# OK6010_DB.net
KiCad netlist of a schematic drawn in Altium Designer
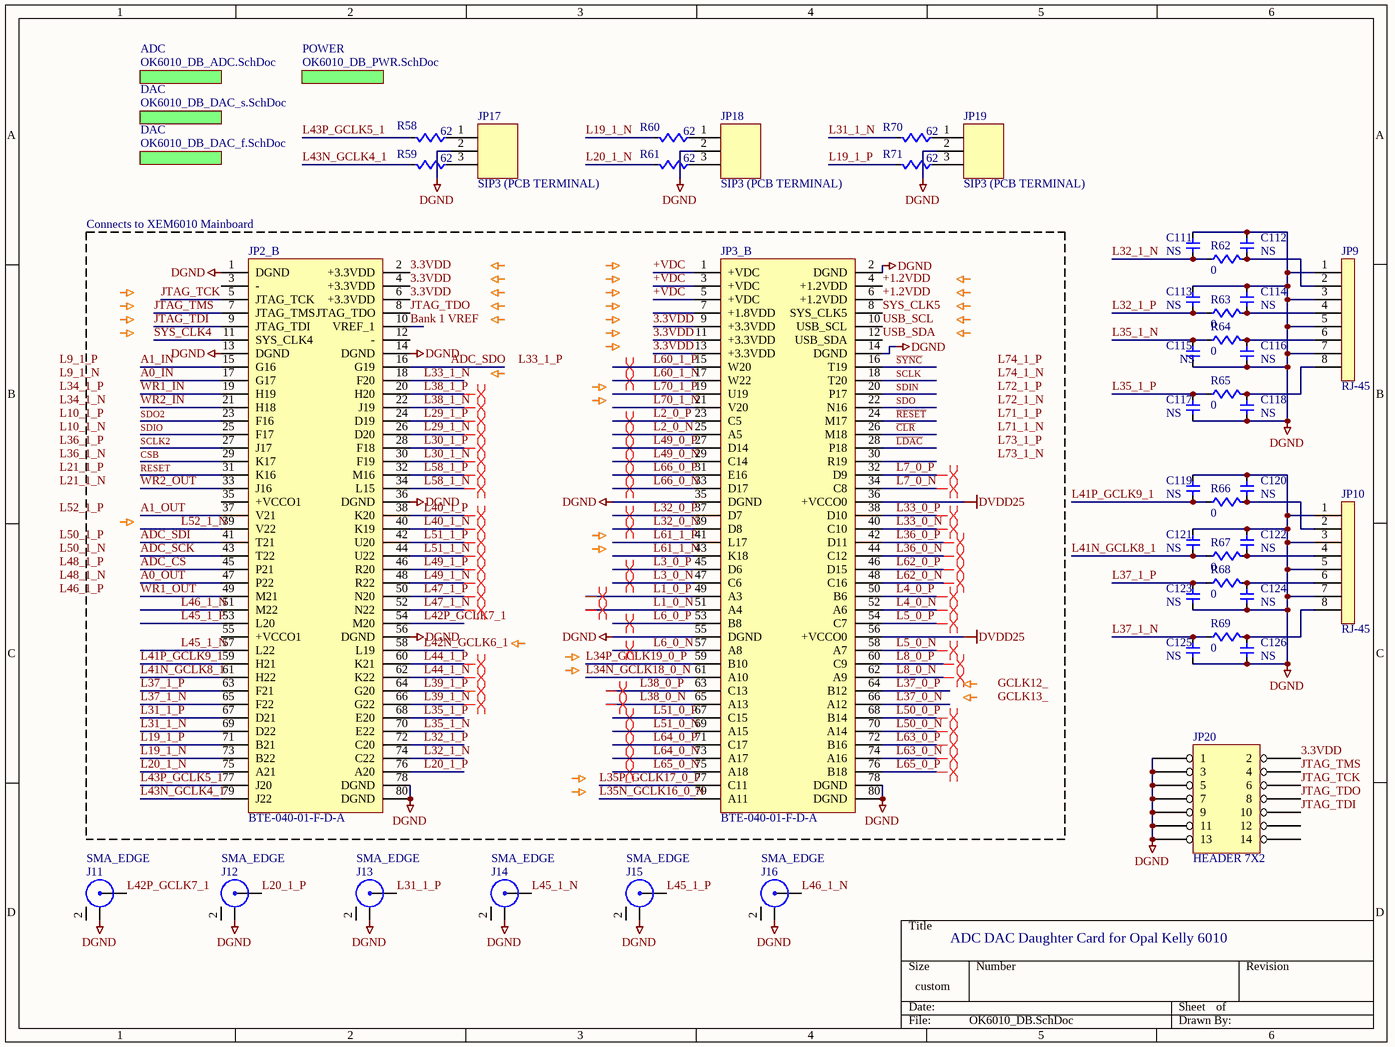
[diagram p0: OK6010_DB.SchDoc]

(export (version "E")
  (design (tool "Eeschema 10.0.6"))
  (components
    (comp (ref "C111")
      (value "NS")
      (footprint "0603w")
      (description "capacitor")
      (libsource (lib "Device02_remote") (part "CAP_SM"))
    )
    (comp (ref "C112")
      (value "NS")
      (footprint "0603w")
      (description "capacitor")
      (libsource (lib "Device02_remote") (part "CAP_SM"))
    )
    (comp (ref "C113")
      (value "NS")
      (footprint "0603w")
      (description "capacitor")
      (libsource (lib "Device02_remote") (part "CAP_SM"))
    )
    (comp (ref "C114")
      (value "NS")
      (footprint "0603w")
      (description "capacitor")
      (libsource (lib "Device02_remote") (part "CAP_SM"))
    )
    (comp (ref "C115")
      (value "NS")
      (footprint "0603w")
      (description "capacitor")
      (libsource (lib "Device02_remote") (part "CAP_SM"))
    )
    (comp (ref "C116")
      (value "NS")
      (footprint "0603w")
      (description "capacitor")
      (libsource (lib "Device02_remote") (part "CAP_SM"))
    )
    (comp (ref "C117")
      (value "NS")
      (footprint "0603w")
      (description "capacitor")
      (libsource (lib "Device02_remote") (part "CAP_SM"))
    )
    (comp (ref "C118")
      (value "NS")
      (footprint "0603w")
      (description "capacitor")
      (libsource (lib "Device02_remote") (part "CAP_SM"))
    )
    (comp (ref "C119")
      (value "NS")
      (footprint "0603w")
      (description "capacitor")
      (libsource (lib "Device02_remote") (part "CAP_SM"))
    )
    (comp (ref "C120")
      (value "NS")
      (footprint "0603w")
      (description "capacitor")
      (libsource (lib "Device02_remote") (part "CAP_SM"))
    )
    (comp (ref "C121")
      (value "NS")
      (footprint "0603w")
      (description "capacitor")
      (libsource (lib "Device02_remote") (part "CAP_SM"))
    )
    (comp (ref "C122")
      (value "NS")
      (footprint "0603w")
      (description "capacitor")
      (libsource (lib "Device02_remote") (part "CAP_SM"))
    )
    (comp (ref "C123")
      (value "NS")
      (footprint "0603w")
      (description "capacitor")
      (libsource (lib "Device02_remote") (part "CAP_SM"))
    )
    (comp (ref "C124")
      (value "NS")
      (footprint "0603w")
      (description "capacitor")
      (libsource (lib "Device02_remote") (part "CAP_SM"))
    )
    (comp (ref "C125")
      (value "NS")
      (footprint "0603w")
      (description "capacitor")
      (libsource (lib "Device02_remote") (part "CAP_SM"))
    )
    (comp (ref "C126")
      (value "NS")
      (footprint "0603w")
      (description "capacitor")
      (libsource (lib "Device02_remote") (part "CAP_SM"))
    )
    (comp (ref "J11")
      (value "SMA_EDGE")
      (footprint "sma_edge")
      (description "sma edge connector")
      (libsource (lib "Device02_remote") (part "SMA_EDGE"))
    )
    (comp (ref "J12")
      (value "SMA_EDGE")
      (footprint "sma_edge")
      (description "sma edge connector")
      (libsource (lib "Device02_remote") (part "SMA_EDGE"))
    )
    (comp (ref "J13")
      (value "SMA_EDGE")
      (footprint "sma_edge")
      (description "sma edge connector")
      (libsource (lib "Device02_remote") (part "SMA_EDGE"))
    )
    (comp (ref "J14")
      (value "SMA_EDGE")
      (footprint "sma_edge")
      (description "sma edge connector")
      (libsource (lib "Device02_remote") (part "SMA_EDGE"))
    )
    (comp (ref "J15")
      (value "SMA_EDGE")
      (footprint "sma_edge")
      (description "sma edge connector")
      (libsource (lib "Device02_remote") (part "SMA_EDGE"))
    )
    (comp (ref "J16")
      (value "SMA_EDGE")
      (footprint "sma_edge")
      (description "sma edge connector")
      (libsource (lib "Device02_remote") (part "SMA_EDGE"))
    )
    (comp (ref "JP2_B")
      (value "BTE-040-01-F-D-A")
      (footprint "BTE-040-01-F-D-A")
      (description "Samtec Connector 0.8mm 80pin")
      (libsource (lib "Device02_remote") (part "BTE-040-01-F-D-A XEM6010_JP2"))
    )
    (comp (ref "JP3_B")
      (value "BTE-040-01-F-D-A")
      (footprint "BTE-040-01-F-D-A")
      (description "Samtec Connector 0.8mm 80pin")
      (libsource (lib "Device02_remote") (part "BTE-040-01-F-D-A XEM6010_JP3"))
    )
    (comp (ref "JP9")
      (value "RJ-45")
      (footprint "SMD_ETHERNET")
      (description "ethernet connector")
      (libsource (lib "Device02_remote") (part "SIP8"))
    )
    (comp (ref "JP10")
      (value "RJ-45")
      (footprint "SMD_ETHERNET")
      (description "ethernet connector")
      (libsource (lib "Device02_remote") (part "SIP8"))
    )
    (comp (ref "JP17")
      (value "SIP3 (PCB TERMINAL)")
      (footprint "SIP3MOLEX")
      (description "3 pin molex connector")
      (libsource (lib "Device02_remote") (part "SIP3 (PCB TERMINAL)"))
    )
    (comp (ref "JP18")
      (value "SIP3 (PCB TERMINAL)")
      (footprint "SIP3MOLEX")
      (description "3 pin molex connector")
      (libsource (lib "Device02_remote") (part "SIP3 (PCB TERMINAL)"))
    )
    (comp (ref "JP19")
      (value "SIP3 (PCB TERMINAL)")
      (footprint "SIP3MOLEX")
      (description "3 pin molex connector")
      (libsource (lib "Device02_remote") (part "SIP3 (PCB TERMINAL)"))
    )
    (comp (ref "JP20")
      (value "HEADER 7X2")
      (footprint "IDC14 SM 2MM")
      (description "14 pin 2mm IDC connector")
      (libsource (lib "Device02_remote") (part "HEADER 7X2"))
    )
    (comp (ref "R58")
      (value "62")
      (footprint "0603w")
      (description "resistor")
      (libsource (lib "Device02_remote") (part "RES_SM"))
    )
    (comp (ref "R59")
      (value "62")
      (footprint "0603w")
      (description "resistor")
      (libsource (lib "Device02_remote") (part "RES_SM"))
    )
    (comp (ref "R60")
      (value "62")
      (footprint "0603w")
      (description "resistor")
      (libsource (lib "Device02_remote") (part "RES_SM"))
    )
    (comp (ref "R61")
      (value "62")
      (footprint "0603w")
      (description "resistor")
      (libsource (lib "Device02_remote") (part "RES_SM"))
    )
    (comp (ref "R62")
      (value "0")
      (footprint "0603w")
      (description "resistor")
      (libsource (lib "Device02_remote") (part "RES_SM"))
    )
    (comp (ref "R63")
      (value "0")
      (footprint "0603w")
      (description "resistor")
      (libsource (lib "Device02_remote") (part "RES_SM"))
    )
    (comp (ref "R64")
      (value "0")
      (footprint "0603w")
      (description "resistor")
      (libsource (lib "Device02_remote") (part "RES_SM"))
    )
    (comp (ref "R65")
      (value "0")
      (footprint "0603w")
      (description "resistor")
      (libsource (lib "Device02_remote") (part "RES_SM"))
    )
    (comp (ref "R66")
      (value "0")
      (footprint "0603w")
      (description "resistor")
      (libsource (lib "Device02_remote") (part "RES_SM"))
    )
    (comp (ref "R67")
      (value "0")
      (footprint "0603w")
      (description "resistor")
      (libsource (lib "Device02_remote") (part "RES_SM"))
    )
    (comp (ref "R68")
      (value "0")
      (footprint "0603w")
      (description "resistor")
      (libsource (lib "Device02_remote") (part "RES_SM"))
    )
    (comp (ref "R69")
      (value "0")
      (footprint "0603w")
      (description "resistor")
      (libsource (lib "Device02_remote") (part "RES_SM"))
    )
    (comp (ref "R70")
      (value "62")
      (footprint "0603w")
      (description "resistor")
      (libsource (lib "Device02_remote") (part "RES_SM"))
    )
    (comp (ref "R71")
      (value "62")
      (footprint "0603w")
      (description "resistor")
      (libsource (lib "Device02_remote") (part "RES_SM"))
    )
  )
  (nets
    (net (code "1") (name "/+1.2VDD") (class "Default")
      (node (ref "JP3_B") (pin "4") (pinfunction "+1.2VDD_4") (pintype "passive"))
      (node (ref "JP3_B") (pin "6") (pinfunction "+1.2VDD_6") (pintype "passive"))
    )
    (net (code "2") (name "/+VDC") (class "Default")
      (node (ref "JP3_B") (pin "1") (pinfunction "+VDC_1") (pintype "passive"))
      (node (ref "JP3_B") (pin "3") (pinfunction "+VDC_3") (pintype "passive"))
      (node (ref "JP3_B") (pin "5") (pinfunction "+VDC_5") (pintype "passive"))
    )
    (net (code "3") (name "/3.3VDD") (class "Default")
      (node (ref "JP20") (pin "2") (pinfunction "2_2") (pintype "passive"))
      (node (ref "JP2_B") (pin "2") (pinfunction "+3.3VDD_2") (pintype "passive"))
      (node (ref "JP2_B") (pin "4") (pinfunction "+3.3VDD_4") (pintype "passive"))
      (node (ref "JP2_B") (pin "6") (pinfunction "+3.3VDD_6") (pintype "passive"))
      (node (ref "JP3_B") (pin "11") (pinfunction "+3.3VDD_11") (pintype "passive"))
      (node (ref "JP3_B") (pin "13") (pinfunction "+3.3VDD_13") (pintype "passive"))
      (node (ref "JP3_B") (pin "9") (pinfunction "+3.3VDD_9") (pintype "passive"))
    )
    (net (code "4") (name "/A0_IN") (class "Default")
      (node (ref "JP2_B") (pin "17") (pinfunction "G17_17") (pintype "passive"))
    )
    (net (code "5") (name "/A0_OUT") (class "Default")
      (node (ref "JP2_B") (pin "47") (pinfunction "P22_47") (pintype "passive"))
    )
    (net (code "6") (name "/A1_IN") (class "Default")
      (node (ref "JP2_B") (pin "15") (pinfunction "G16_15") (pintype "passive"))
    )
    (net (code "7") (name "/A1_OUT") (class "Default")
      (node (ref "JP2_B") (pin "37") (pinfunction "V21_37") (pintype "passive"))
    )
    (net (code "8") (name "/ADC_CS") (class "Default")
      (node (ref "JP2_B") (pin "45") (pinfunction "P21_45") (pintype "passive"))
    )
    (net (code "9") (name "/ADC_SCK") (class "Default")
      (node (ref "JP2_B") (pin "43") (pinfunction "T22_43") (pintype "passive"))
    )
    (net (code "10") (name "/ADC_SDI") (class "Default")
      (node (ref "JP2_B") (pin "41") (pinfunction "T21_41") (pintype "passive"))
    )
    (net (code "11") (name "/ADC_SDO") (class "Default")
      (node (ref "JP2_B") (pin "16") (pinfunction "G19_16") (pintype "passive"))
    )
    (net (code "12") (name "/Bank 1 VREF") (class "Default")
      (node (ref "JP2_B") (pin "10") (pinfunction "VREF_1_10") (pintype "passive"))
    )
    (net (code "13") (name "/CSB") (class "Default")
      (node (ref "JP2_B") (pin "29") (pinfunction "K17_29") (pintype "passive"))
    )
    (net (code "16") (name "/JTAG_TCK") (class "Default")
      (node (ref "JP20") (pin "6") (pinfunction "6_6") (pintype "passive"))
      (node (ref "JP2_B") (pin "5") (pinfunction "JTAG_TCK_5") (pintype "passive"))
    )
    (net (code "17") (name "/JTAG_TDI") (class "Default")
      (node (ref "JP20") (pin "10") (pinfunction "10_10") (pintype "passive"))
      (node (ref "JP2_B") (pin "9") (pinfunction "JTAG_TDI_9") (pintype "passive"))
    )
    (net (code "18") (name "/JTAG_TDO") (class "Default")
      (node (ref "JP20") (pin "8") (pinfunction "8_8") (pintype "passive"))
      (node (ref "JP2_B") (pin "8") (pinfunction "JTAG_TDO_8") (pintype "passive"))
    )
    (net (code "19") (name "/JTAG_TMS") (class "Default")
      (node (ref "JP20") (pin "4") (pinfunction "4_4") (pintype "passive"))
      (node (ref "JP2_B") (pin "7") (pinfunction "JTAG_TMS_7") (pintype "passive"))
    )
    (net (code "20") (name "/L1_0_N") (class "Default")
      (node (ref "JP3_B") (pin "51") (pinfunction "A4_51") (pintype "passive"))
    )
    (net (code "21") (name "/L1_0_P") (class "Default")
      (node (ref "JP3_B") (pin "49") (pinfunction "A3_49") (pintype "passive"))
    )
    (net (code "22") (name "/L2_0_N") (class "Default")
      (node (ref "JP3_B") (pin "25") (pinfunction "A5_25") (pintype "passive"))
    )
    (net (code "23") (name "/L2_0_P") (class "Default")
      (node (ref "JP3_B") (pin "23") (pinfunction "C5_23") (pintype "passive"))
    )
    (net (code "24") (name "/L3_0_N") (class "Default")
      (node (ref "JP3_B") (pin "47") (pinfunction "C6_47") (pintype "passive"))
    )
    (net (code "25") (name "/L3_0_P") (class "Default")
      (node (ref "JP3_B") (pin "45") (pinfunction "D6_45") (pintype "passive"))
    )
    (net (code "26") (name "/L4_0_N") (class "Default")
      (node (ref "JP3_B") (pin "52") (pinfunction "A6_52") (pintype "passive"))
    )
    (net (code "27") (name "/L4_0_P") (class "Default")
      (node (ref "JP3_B") (pin "50") (pinfunction "B6_50") (pintype "passive"))
    )
    (net (code "28") (name "/L5_0_N") (class "Default")
      (node (ref "JP3_B") (pin "58") (pinfunction "A7_58") (pintype "passive"))
    )
    (net (code "29") (name "/L5_0_P") (class "Default")
      (node (ref "JP3_B") (pin "54") (pinfunction "C7_54") (pintype "passive"))
    )
    (net (code "30") (name "/L6_0_N") (class "Default")
      (node (ref "JP3_B") (pin "57") (pinfunction "A8_57") (pintype "passive"))
    )
    (net (code "31") (name "/L6_0_P") (class "Default")
      (node (ref "JP3_B") (pin "53") (pinfunction "B8_53") (pintype "passive"))
    )
    (net (code "32") (name "/L7_0_N") (class "Default")
      (node (ref "JP3_B") (pin "34") (pinfunction "C8_34") (pintype "passive"))
    )
    (net (code "33") (name "/L7_0_P") (class "Default")
      (node (ref "JP3_B") (pin "32") (pinfunction "D9_32") (pintype "passive"))
    )
    (net (code "34") (name "/L8_0_N") (class "Default")
      (node (ref "JP3_B") (pin "62") (pinfunction "A9_62") (pintype "passive"))
    )
    (net (code "35") (name "/L8_0_P") (class "Default")
      (node (ref "JP3_B") (pin "60") (pinfunction "C9_60") (pintype "passive"))
    )
    (net (code "40") (name "/L19_1_N") (class "Default")
      (node (ref "JP2_B") (pin "73") (pinfunction "B22_73") (pintype "passive"))
      (node (ref "R60") (pin "2") (pintype "passive"))
    )
    (net (code "41") (name "/L19_1_P") (class "Default")
      (node (ref "JP2_B") (pin "71") (pinfunction "B21_71") (pintype "passive"))
      (node (ref "R71") (pin "2") (pintype "passive"))
    )
    (net (code "42") (name "/L20_1_N") (class "Default")
      (node (ref "JP2_B") (pin "75") (pinfunction "A21_75") (pintype "passive"))
      (node (ref "R61") (pin "2") (pintype "passive"))
    )
    (net (code "43") (name "/L20_1_P") (class "Default")
      (node (ref "J12") (pin "1") (pinfunction "signal_1") (pintype "passive"))
      (node (ref "JP2_B") (pin "76") (pinfunction "A20_76") (pintype "passive"))
    )
    (net (code "46") (name "/L29_1_N") (class "Default")
      (node (ref "JP2_B") (pin "26") (pinfunction "D20_26") (pintype "passive"))
    )
    (net (code "47") (name "/L29_1_P") (class "Default")
      (node (ref "JP2_B") (pin "24") (pinfunction "D19_24") (pintype "passive"))
    )
    (net (code "48") (name "/L30_1_N") (class "Default")
      (node (ref "JP2_B") (pin "30") (pinfunction "F19_30") (pintype "passive"))
    )
    (net (code "49") (name "/L30_1_P") (class "Default")
      (node (ref "JP2_B") (pin "28") (pinfunction "F18_28") (pintype "passive"))
    )
    (net (code "50") (name "/L31_1_N") (class "Default")
      (node (ref "JP2_B") (pin "69") (pinfunction "D22_69") (pintype "passive"))
      (node (ref "R70") (pin "2") (pintype "passive"))
    )
    (net (code "51") (name "/L31_1_P") (class "Default")
      (node (ref "J13") (pin "1") (pinfunction "signal_1") (pintype "passive"))
      (node (ref "JP2_B") (pin "67") (pinfunction "D21_67") (pintype "passive"))
    )
    (net (code "52") (name "/L32_0_N") (class "Default")
      (node (ref "JP3_B") (pin "39") (pinfunction "D8_39") (pintype "passive"))
    )
    (net (code "53") (name "/L32_0_P") (class "Default")
      (node (ref "JP3_B") (pin "37") (pinfunction "D7_37") (pintype "passive"))
    )
    (net (code "54") (name "/L32_1_N") (class "Default")
      (node (ref "C111") (pin "2") (pintype "passive"))
      (node (ref "JP2_B") (pin "74") (pinfunction "C22_74") (pintype "passive"))
      (node (ref "R62") (pin "1") (pintype "passive"))
    )
    (net (code "55") (name "/L32_1_P") (class "Default")
      (node (ref "C113") (pin "2") (pintype "passive"))
      (node (ref "JP2_B") (pin "72") (pinfunction "C20_72") (pintype "passive"))
      (node (ref "R63") (pin "1") (pintype "passive"))
    )
    (net (code "56") (name "/L33_0_N") (class "Default")
      (node (ref "JP3_B") (pin "40") (pinfunction "C10_40") (pintype "passive"))
    )
    (net (code "57") (name "/L33_0_P") (class "Default")
      (node (ref "JP3_B") (pin "38") (pinfunction "D10_38") (pintype "passive"))
    )
    (net (code "58") (name "/L33_1_N") (class "Default")
      (node (ref "JP2_B") (pin "18") (pinfunction "F20_18") (pintype "passive"))
    )
    (net (code "60") (name "/L34N_GCLK18_0_N") (class "Default")
      (node (ref "JP3_B") (pin "61") (pinfunction "A10_61") (pintype "passive"))
    )
    (net (code "61") (name "/L34P_GCLK19_0_P") (class "Default")
      (node (ref "JP3_B") (pin "59") (pinfunction "B10_59") (pintype "passive"))
    )
    (net (code "64") (name "/L35N_GCLK16_0_N") (class "Default")
      (node (ref "JP3_B") (pin "79") (pinfunction "A11_79") (pintype "passive"))
    )
    (net (code "65") (name "/L35P_GCLK17_0_P") (class "Default")
      (node (ref "JP3_B") (pin "77") (pinfunction "C11_77") (pintype "passive"))
    )
    (net (code "66") (name "/L35_1_N") (class "Default")
      (node (ref "C115") (pin "1") (pintype "passive"))
      (node (ref "JP2_B") (pin "70") (pinfunction "E22_70") (pintype "passive"))
      (node (ref "R64") (pin "1") (pintype "passive"))
    )
    (net (code "67") (name "/L35_1_P") (class "Default")
      (node (ref "C117") (pin "1") (pintype "passive"))
      (node (ref "JP2_B") (pin "68") (pinfunction "E20_68") (pintype "passive"))
      (node (ref "R65") (pin "1") (pintype "passive"))
    )
    (net (code "68") (name "/L36_0_N") (class "Default")
      (node (ref "JP3_B") (pin "44") (pinfunction "C12_44") (pintype "passive"))
    )
    (net (code "69") (name "/L36_0_P") (class "Default")
      (node (ref "JP3_B") (pin "42") (pinfunction "D11_42") (pintype "passive"))
    )
    (net (code "72") (name "/L37_0_N") (class "Default")
      (node (ref "JP3_B") (pin "66") (pinfunction "A12_66") (pintype "passive"))
    )
    (net (code "73") (name "/L37_0_P") (class "Default")
      (node (ref "JP3_B") (pin "64") (pinfunction "B12_64") (pintype "passive"))
    )
    (net (code "74") (name "/L37_1_N") (class "Default")
      (node (ref "C125") (pin "1") (pintype "passive"))
      (node (ref "JP2_B") (pin "65") (pinfunction "F22_65") (pintype "passive"))
      (node (ref "R69") (pin "1") (pintype "passive"))
    )
    (net (code "75") (name "/L37_1_P") (class "Default")
      (node (ref "C123") (pin "1") (pintype "passive"))
      (node (ref "JP2_B") (pin "63") (pinfunction "F21_63") (pintype "passive"))
      (node (ref "R68") (pin "1") (pintype "passive"))
    )
    (net (code "76") (name "/L38_0_N") (class "Default")
      (node (ref "JP3_B") (pin "65") (pinfunction "A13_65") (pintype "passive"))
    )
    (net (code "77") (name "/L38_0_P") (class "Default")
      (node (ref "JP3_B") (pin "63") (pinfunction "C13_63") (pintype "passive"))
    )
    (net (code "78") (name "/L38_1_N") (class "Default")
      (node (ref "JP2_B") (pin "22") (pinfunction "J19_22") (pintype "passive"))
    )
    (net (code "79") (name "/L38_1_P") (class "Default")
      (node (ref "JP2_B") (pin "20") (pinfunction "H20_20") (pintype "passive"))
    )
    (net (code "80") (name "/L39_1_N") (class "Default")
      (node (ref "JP2_B") (pin "66") (pinfunction "G22_66") (pintype "passive"))
    )
    (net (code "81") (name "/L39_1_P") (class "Default")
      (node (ref "JP2_B") (pin "64") (pinfunction "G20_64") (pintype "passive"))
    )
    (net (code "82") (name "/L40_1_N") (class "Default")
      (node (ref "JP2_B") (pin "40") (pinfunction "K19_40") (pintype "passive"))
    )
    (net (code "83") (name "/L40_1_P") (class "Default")
      (node (ref "JP2_B") (pin "38") (pinfunction "K20_38") (pintype "passive"))
    )
    (net (code "84") (name "/L41N_GCLK8_1") (class "Default")
      (node (ref "C121") (pin "2") (pintype "passive"))
      (node (ref "JP2_B") (pin "61") (pinfunction "H22_61") (pintype "passive"))
      (node (ref "R67") (pin "1") (pintype "passive"))
    )
    (net (code "85") (name "/L41P_GCLK9_1") (class "Default")
      (node (ref "C119") (pin "2") (pintype "passive"))
      (node (ref "JP2_B") (pin "59") (pinfunction "H21_59") (pintype "passive"))
      (node (ref "R66") (pin "1") (pintype "passive"))
    )
    (net (code "86") (name "/L42N_GCLK6_1") (class "Default")
      (node (ref "JP2_B") (pin "58") (pinfunction "L19_58") (pintype "passive"))
    )
    (net (code "87") (name "/L42P_GCLK7_1") (class "Default")
      (node (ref "J11") (pin "1") (pinfunction "signal_1") (pintype "passive"))
      (node (ref "JP2_B") (pin "54") (pinfunction "M20_54") (pintype "passive"))
    )
    (net (code "88") (name "/L43N_GCLK4_1") (class "Default")
      (node (ref "JP2_B") (pin "79") (pinfunction "J22_79") (pintype "passive"))
      (node (ref "R59") (pin "2") (pintype "passive"))
    )
    (net (code "89") (name "/L43P_GCLK5_1") (class "Default")
      (node (ref "JP2_B") (pin "77") (pinfunction "J20_77") (pintype "passive"))
      (node (ref "R58") (pin "2") (pintype "passive"))
    )
    (net (code "90") (name "/L44_1_N") (class "Default")
      (node (ref "JP2_B") (pin "62") (pinfunction "K22_62") (pintype "passive"))
    )
    (net (code "91") (name "/L44_1_P") (class "Default")
      (node (ref "JP2_B") (pin "60") (pinfunction "K21_60") (pintype "passive"))
    )
    (net (code "92") (name "/L45_1_N") (class "Default")
      (node (ref "J14") (pin "1") (pinfunction "signal_1") (pintype "passive"))
      (node (ref "JP2_B") (pin "57") (pinfunction "L22_57") (pintype "passive"))
    )
    (net (code "93") (name "/L45_1_P") (class "Default")
      (node (ref "J15") (pin "1") (pinfunction "signal_1") (pintype "passive"))
      (node (ref "JP2_B") (pin "53") (pinfunction "L20_53") (pintype "passive"))
    )
    (net (code "94") (name "/L46_1_N") (class "Default")
      (node (ref "J16") (pin "1") (pinfunction "signal_1") (pintype "passive"))
      (node (ref "JP2_B") (pin "51") (pinfunction "M22_51") (pintype "passive"))
    )
    (net (code "96") (name "/L47_1_N") (class "Default")
      (node (ref "JP2_B") (pin "52") (pinfunction "N22_52") (pintype "passive"))
    )
    (net (code "97") (name "/L47_1_P") (class "Default")
      (node (ref "JP2_B") (pin "50") (pinfunction "N20_50") (pintype "passive"))
    )
    (net (code "100") (name "/L49_0_N") (class "Default")
      (node (ref "JP3_B") (pin "29") (pinfunction "C14_29") (pintype "passive"))
    )
    (net (code "101") (name "/L49_0_P") (class "Default")
      (node (ref "JP3_B") (pin "27") (pinfunction "D14_27") (pintype "passive"))
    )
    (net (code "102") (name "/L49_1_N") (class "Default")
      (node (ref "JP2_B") (pin "48") (pinfunction "R22_48") (pintype "passive"))
    )
    (net (code "103") (name "/L49_1_P") (class "Default")
      (node (ref "JP2_B") (pin "46") (pinfunction "R20_46") (pintype "passive"))
    )
    (net (code "104") (name "/L50_0_N") (class "Default")
      (node (ref "JP3_B") (pin "70") (pinfunction "A14_70") (pintype "passive"))
    )
    (net (code "105") (name "/L50_0_P") (class "Default")
      (node (ref "JP3_B") (pin "68") (pinfunction "B14_68") (pintype "passive"))
    )
    (net (code "108") (name "/L51_0_N") (class "Default")
      (node (ref "JP3_B") (pin "69") (pinfunction "A15_69") (pintype "passive"))
    )
    (net (code "109") (name "/L51_0_P") (class "Default")
      (node (ref "JP3_B") (pin "67") (pinfunction "C15_67") (pintype "passive"))
    )
    (net (code "110") (name "/L51_1_N") (class "Default")
      (node (ref "JP2_B") (pin "44") (pinfunction "U22_44") (pintype "passive"))
    )
    (net (code "111") (name "/L51_1_P") (class "Default")
      (node (ref "JP2_B") (pin "42") (pinfunction "U20_42") (pintype "passive"))
    )
    (net (code "112") (name "/L52_1_N") (class "Default")
      (node (ref "JP2_B") (pin "39") (pinfunction "V22_39") (pintype "passive"))
    )
    (net (code "114") (name "/L58_1_N") (class "Default")
      (node (ref "JP2_B") (pin "34") (pinfunction "L15_34") (pintype "passive"))
    )
    (net (code "115") (name "/L58_1_P") (class "Default")
      (node (ref "JP2_B") (pin "32") (pinfunction "M16_32") (pintype "passive"))
    )
    (net (code "116") (name "/L60_1_N") (class "Default")
      (node (ref "JP3_B") (pin "17") (pinfunction "W22_17") (pintype "passive"))
    )
    (net (code "117") (name "/L60_1_P") (class "Default")
      (node (ref "JP3_B") (pin "15") (pinfunction "W20_15") (pintype "passive"))
    )
    (net (code "118") (name "/L61_1_N") (class "Default")
      (node (ref "JP3_B") (pin "43") (pinfunction "K18_43") (pintype "passive"))
    )
    (net (code "119") (name "/L61_1_P") (class "Default")
      (node (ref "JP3_B") (pin "41") (pinfunction "L17_41") (pintype "passive"))
    )
    (net (code "120") (name "/L62_0_N") (class "Default")
      (node (ref "JP3_B") (pin "48") (pinfunction "C16_48") (pintype "passive"))
    )
    (net (code "121") (name "/L62_0_P") (class "Default")
      (node (ref "JP3_B") (pin "46") (pinfunction "D15_46") (pintype "passive"))
    )
    (net (code "122") (name "/L63_0_N") (class "Default")
      (node (ref "JP3_B") (pin "74") (pinfunction "A16_74") (pintype "passive"))
    )
    (net (code "123") (name "/L63_0_P") (class "Default")
      (node (ref "JP3_B") (pin "72") (pinfunction "B16_72") (pintype "passive"))
    )
    (net (code "124") (name "/L64_0_N") (class "Default")
      (node (ref "JP3_B") (pin "73") (pinfunction "A17_73") (pintype "passive"))
    )
    (net (code "125") (name "/L64_0_P") (class "Default")
      (node (ref "JP3_B") (pin "71") (pinfunction "C17_71") (pintype "passive"))
    )
    (net (code "126") (name "/L65_0_N") (class "Default")
      (node (ref "JP3_B") (pin "75") (pinfunction "A18_75") (pintype "passive"))
    )
    (net (code "127") (name "/L65_0_P") (class "Default")
      (node (ref "JP3_B") (pin "76") (pinfunction "B18_76") (pintype "passive"))
    )
    (net (code "128") (name "/L66_0_N") (class "Default")
      (node (ref "JP3_B") (pin "33") (pinfunction "D17_33") (pintype "passive"))
    )
    (net (code "129") (name "/L66_0_P") (class "Default")
      (node (ref "JP3_B") (pin "31") (pinfunction "E16_31") (pintype "passive"))
    )
    (net (code "130") (name "/L70_1_N") (class "Default")
      (node (ref "JP3_B") (pin "21") (pinfunction "V20_21") (pintype "passive"))
    )
    (net (code "131") (name "/L70_1_P") (class "Default")
      (node (ref "JP3_B") (pin "19") (pinfunction "U19_19") (pintype "passive"))
    )
    (net (code "140") (name "/RESET") (class "Default")
      (node (ref "JP2_B") (pin "31") (pinfunction "K16_31") (pintype "passive"))
    )
    (net (code "141") (name "/SCLK") (class "Default")
      (node (ref "JP3_B") (pin "18") (pinfunction "T20_18") (pintype "passive"))
    )
    (net (code "142") (name "/SCLK2") (class "Default")
      (node (ref "JP2_B") (pin "27") (pinfunction "J17_27") (pintype "passive"))
    )
    (net (code "143") (name "/SDIN") (class "Default")
      (node (ref "JP3_B") (pin "20") (pinfunction "P17_20") (pintype "passive"))
    )
    (net (code "144") (name "/SDIO") (class "Default")
      (node (ref "JP2_B") (pin "25") (pinfunction "F17_25") (pintype "passive"))
    )
    (net (code "145") (name "/SDO") (class "Default")
      (node (ref "JP3_B") (pin "22") (pinfunction "N16_22") (pintype "passive"))
    )
    (net (code "146") (name "/SDO2") (class "Default")
      (node (ref "JP2_B") (pin "23") (pinfunction "F16_23") (pintype "passive"))
    )
    (net (code "147") (name "/SYS_CLK4") (class "Default")
      (node (ref "JP2_B") (pin "11") (pinfunction "SYS_CLK4_11") (pintype "passive"))
    )
    (net (code "148") (name "/SYS_CLK5") (class "Default")
      (node (ref "JP3_B") (pin "8") (pinfunction "SYS_CLK5_8") (pintype "passive"))
    )
    (net (code "149") (name "/USB_SCL") (class "Default")
      (node (ref "JP3_B") (pin "10") (pinfunction "USB_SCL_10") (pintype "passive"))
    )
    (net (code "150") (name "/USB_SDA") (class "Default")
      (node (ref "JP3_B") (pin "12") (pinfunction "USB_SDA_12") (pintype "passive"))
    )
    (net (code "151") (name "/WR1_IN") (class "Default")
      (node (ref "JP2_B") (pin "19") (pinfunction "H19_19") (pintype "passive"))
    )
    (net (code "152") (name "/WR1_OUT") (class "Default")
      (node (ref "JP2_B") (pin "49") (pinfunction "M21_49") (pintype "passive"))
    )
    (net (code "153") (name "/WR2_IN") (class "Default")
      (node (ref "JP2_B") (pin "21") (pinfunction "H18_21") (pintype "passive"))
    )
    (net (code "154") (name "/WR2_OUT") (class "Default")
      (node (ref "JP2_B") (pin "33") (pinfunction "J16_33") (pintype "passive"))
    )
    (net (code "155") (name "/~{CLR}") (class "Default")
      (node (ref "JP3_B") (pin "26") (pinfunction "M18_26") (pintype "passive"))
    )
    (net (code "156") (name "/~{LDAC}") (class "Default")
      (node (ref "JP3_B") (pin "28") (pinfunction "P18_28") (pintype "passive"))
    )
    (net (code "157") (name "/~{RESET}") (class "Default")
      (node (ref "JP3_B") (pin "24") (pinfunction "M17_24") (pintype "passive"))
    )
    (net (code "158") (name "/~{SYNC}") (class "Default")
      (node (ref "JP3_B") (pin "16") (pinfunction "T19_16") (pintype "passive"))
    )
    (net (code "160") (name "DGND") (class "Default")
      (node (ref "C111") (pin "1") (pintype "passive"))
      (node (ref "C112") (pin "1") (pintype "passive"))
      (node (ref "C113") (pin "1") (pintype "passive"))
      (node (ref "C114") (pin "1") (pintype "passive"))
      (node (ref "C115") (pin "2") (pintype "passive"))
      (node (ref "C116") (pin "2") (pintype "passive"))
      (node (ref "C117") (pin "2") (pintype "passive"))
      (node (ref "C118") (pin "2") (pintype "passive"))
      (node (ref "C119") (pin "1") (pintype "passive"))
      (node (ref "C120") (pin "1") (pintype "passive"))
      (node (ref "C121") (pin "1") (pintype "passive"))
      (node (ref "C122") (pin "1") (pintype "passive"))
      (node (ref "C123") (pin "2") (pintype "passive"))
      (node (ref "C124") (pin "2") (pintype "passive"))
      (node (ref "C125") (pin "2") (pintype "passive"))
      (node (ref "C126") (pin "2") (pintype "passive"))
      (node (ref "J11") (pin "2") (pinfunction "ground_2") (pintype "passive"))
      (node (ref "J12") (pin "2") (pinfunction "ground_2") (pintype "passive"))
      (node (ref "J13") (pin "2") (pinfunction "ground_2") (pintype "passive"))
      (node (ref "J14") (pin "2") (pinfunction "ground_2") (pintype "passive"))
      (node (ref "J15") (pin "2") (pinfunction "ground_2") (pintype "passive"))
      (node (ref "J16") (pin "2") (pinfunction "ground_2") (pintype "passive"))
      (node (ref "JP10") (pin "1") (pintype "passive"))
      (node (ref "JP10") (pin "3") (pintype "passive"))
      (node (ref "JP10") (pin "5") (pintype "passive"))
      (node (ref "JP10") (pin "7") (pintype "passive"))
      (node (ref "JP17") (pin "2") (pintype "passive"))
      (node (ref "JP18") (pin "2") (pintype "passive"))
      (node (ref "JP19") (pin "2") (pintype "passive"))
      (node (ref "JP20") (pin "1") (pinfunction "1_1") (pintype "passive"))
      (node (ref "JP20") (pin "11") (pinfunction "11_11") (pintype "passive"))
      (node (ref "JP20") (pin "13") (pinfunction "13_13") (pintype "passive"))
      (node (ref "JP20") (pin "3") (pinfunction "3_3") (pintype "passive"))
      (node (ref "JP20") (pin "5") (pinfunction "5_5") (pintype "passive"))
      (node (ref "JP20") (pin "7") (pinfunction "7_7") (pintype "passive"))
      (node (ref "JP20") (pin "9") (pinfunction "9_9") (pintype "passive"))
      (node (ref "JP2_B") (pin "1") (pinfunction "DGND_1") (pintype "passive"))
      (node (ref "JP2_B") (pin "13") (pinfunction "DGND_13") (pintype "passive"))
      (node (ref "JP2_B") (pin "14") (pinfunction "DGND_14") (pintype "passive"))
      (node (ref "JP2_B") (pin "36") (pinfunction "DGND_36") (pintype "passive"))
      (node (ref "JP2_B") (pin "56") (pinfunction "DGND_56") (pintype "passive"))
      (node (ref "JP2_B") (pin "78") (pinfunction "DGND_78") (pintype "passive"))
      (node (ref "JP2_B") (pin "80") (pinfunction "DGND_80") (pintype "passive"))
      (node (ref "JP3_B") (pin "14") (pinfunction "DGND_14") (pintype "passive"))
      (node (ref "JP3_B") (pin "2") (pinfunction "DGND_2") (pintype "passive"))
      (node (ref "JP3_B") (pin "35") (pinfunction "DGND_35") (pintype "passive"))
      (node (ref "JP3_B") (pin "55") (pinfunction "DGND_55") (pintype "passive"))
      (node (ref "JP3_B") (pin "78") (pinfunction "DGND_78") (pintype "passive"))
      (node (ref "JP3_B") (pin "80") (pinfunction "DGND_80") (pintype "passive"))
      (node (ref "JP9") (pin "1") (pintype "passive"))
      (node (ref "JP9") (pin "3") (pintype "passive"))
      (node (ref "JP9") (pin "5") (pintype "passive"))
      (node (ref "JP9") (pin "7") (pintype "passive"))
    )
    (net (code "161") (name "DVDD25") (class "Default")
      (node (ref "JP3_B") (pin "36") (pinfunction "+VCCO0_36") (pintype "passive"))
      (node (ref "JP3_B") (pin "56") (pinfunction "+VCCO0_56") (pintype "passive"))
    )
    (net (code "162") (name "Net-(C112-Pad2)") (class "Default")
      (node (ref "C112") (pin "2") (pintype "passive"))
      (node (ref "JP9") (pin "2") (pintype "passive"))
      (node (ref "R62") (pin "2") (pintype "passive"))
    )
    (net (code "163") (name "Net-(C114-Pad2)") (class "Default")
      (node (ref "C114") (pin "2") (pintype "passive"))
      (node (ref "JP9") (pin "4") (pintype "passive"))
      (node (ref "R63") (pin "2") (pintype "passive"))
    )
    (net (code "164") (name "Net-(C116-Pad1)") (class "Default")
      (node (ref "C116") (pin "1") (pintype "passive"))
      (node (ref "JP9") (pin "6") (pintype "passive"))
      (node (ref "R64") (pin "2") (pintype "passive"))
    )
    (net (code "165") (name "Net-(C118-Pad1)") (class "Default")
      (node (ref "C118") (pin "1") (pintype "passive"))
      (node (ref "JP9") (pin "8") (pintype "passive"))
      (node (ref "R65") (pin "2") (pintype "passive"))
    )
    (net (code "166") (name "Net-(C120-Pad2)") (class "Default")
      (node (ref "C120") (pin "2") (pintype "passive"))
      (node (ref "JP10") (pin "2") (pintype "passive"))
      (node (ref "R66") (pin "2") (pintype "passive"))
    )
    (net (code "167") (name "Net-(C122-Pad2)") (class "Default")
      (node (ref "C122") (pin "2") (pintype "passive"))
      (node (ref "JP10") (pin "4") (pintype "passive"))
      (node (ref "R67") (pin "2") (pintype "passive"))
    )
    (net (code "168") (name "Net-(C124-Pad1)") (class "Default")
      (node (ref "C124") (pin "1") (pintype "passive"))
      (node (ref "JP10") (pin "6") (pintype "passive"))
      (node (ref "R68") (pin "2") (pintype "passive"))
    )
    (net (code "169") (name "Net-(C126-Pad1)") (class "Default")
      (node (ref "C126") (pin "1") (pintype "passive"))
      (node (ref "JP10") (pin "8") (pintype "passive"))
      (node (ref "R69") (pin "2") (pintype "passive"))
    )
    (net (code "170") (name "Net-(JP17-Pad1)") (class "Default")
      (node (ref "JP17") (pin "1") (pintype "passive"))
      (node (ref "R58") (pin "1") (pintype "passive"))
    )
    (net (code "171") (name "Net-(JP17-Pad3)") (class "Default")
      (node (ref "JP17") (pin "3") (pintype "passive"))
      (node (ref "R59") (pin "1") (pintype "passive"))
    )
    (net (code "172") (name "Net-(JP18-Pad1)") (class "Default")
      (node (ref "JP18") (pin "1") (pintype "passive"))
      (node (ref "R60") (pin "1") (pintype "passive"))
    )
    (net (code "173") (name "Net-(JP18-Pad3)") (class "Default")
      (node (ref "JP18") (pin "3") (pintype "passive"))
      (node (ref "R61") (pin "1") (pintype "passive"))
    )
    (net (code "174") (name "Net-(JP19-Pad1)") (class "Default")
      (node (ref "JP19") (pin "1") (pintype "passive"))
      (node (ref "R70") (pin "1") (pintype "passive"))
    )
    (net (code "175") (name "Net-(JP19-Pad3)") (class "Default")
      (node (ref "JP19") (pin "3") (pintype "passive"))
      (node (ref "R71") (pin "1") (pintype "passive"))
    )
    (net (code "176") (name "unconnected-(J11-Pad2)") (class "Default")
      (node (ref "J11") (pin "2") (pintype "passive"))
    )
    (net (code "177") (name "unconnected-(J12-Pad2)") (class "Default")
      (node (ref "J12") (pin "2") (pintype "passive"))
    )
    (net (code "178") (name "unconnected-(J13-Pad2)") (class "Default")
      (node (ref "J13") (pin "2") (pintype "passive"))
    )
    (net (code "179") (name "unconnected-(J14-Pad2)") (class "Default")
      (node (ref "J14") (pin "2") (pintype "passive"))
    )
    (net (code "180") (name "unconnected-(J15-Pad2)") (class "Default")
      (node (ref "J15") (pin "2") (pintype "passive"))
    )
    (net (code "181") (name "unconnected-(J16-Pad2)") (class "Default")
      (node (ref "J16") (pin "2") (pintype "passive"))
    )
    (net (code "182") (name "unconnected-(JP2_B-+VCCO1-Pad35)") (class "Default")
      (node (ref "JP2_B") (pin "35") (pinfunction "+VCCO1_35") (pintype "passive"))
    )
    (net (code "183") (name "unconnected-(JP2_B-+VCCO1-Pad55)") (class "Default")
      (node (ref "JP2_B") (pin "55") (pinfunction "+VCCO1_55") (pintype "passive"))
    )
    (net (code "184") (name "unconnected-(JP2_B---Pad3)") (class "Default")
      (node (ref "JP2_B") (pin "3") (pinfunction "-_3") (pintype "passive"))
    )
    (net (code "185") (name "unconnected-(JP2_B---Pad12)") (class "Default")
      (node (ref "JP2_B") (pin "12") (pinfunction "-_12") (pintype "passive"))
    )
    (net (code "186") (name "unconnected-(JP3_B-+1.8VDD-Pad7)") (class "Default")
      (node (ref "JP3_B") (pin "7") (pinfunction "+1.8VDD_7") (pintype "passive"))
    )
    (net (code "187") (name "unconnected-(JP3_B-R19-Pad30)") (class "Default")
      (node (ref "JP3_B") (pin "30") (pinfunction "R19_30") (pintype "passive"))
    )
    (net (code "188") (name "unconnected-(JP20-Pad12)") (class "Default")
      (node (ref "JP20") (pin "12") (pinfunction "12_12") (pintype "passive"))
    )
    (net (code "189") (name "unconnected-(JP20-Pad14)") (class "Default")
      (node (ref "JP20") (pin "14") (pinfunction "14_14") (pintype "passive"))
    )
  )
)
